# Bread_2040.net
KiCad netlist of a schematic drawn in EAGLE
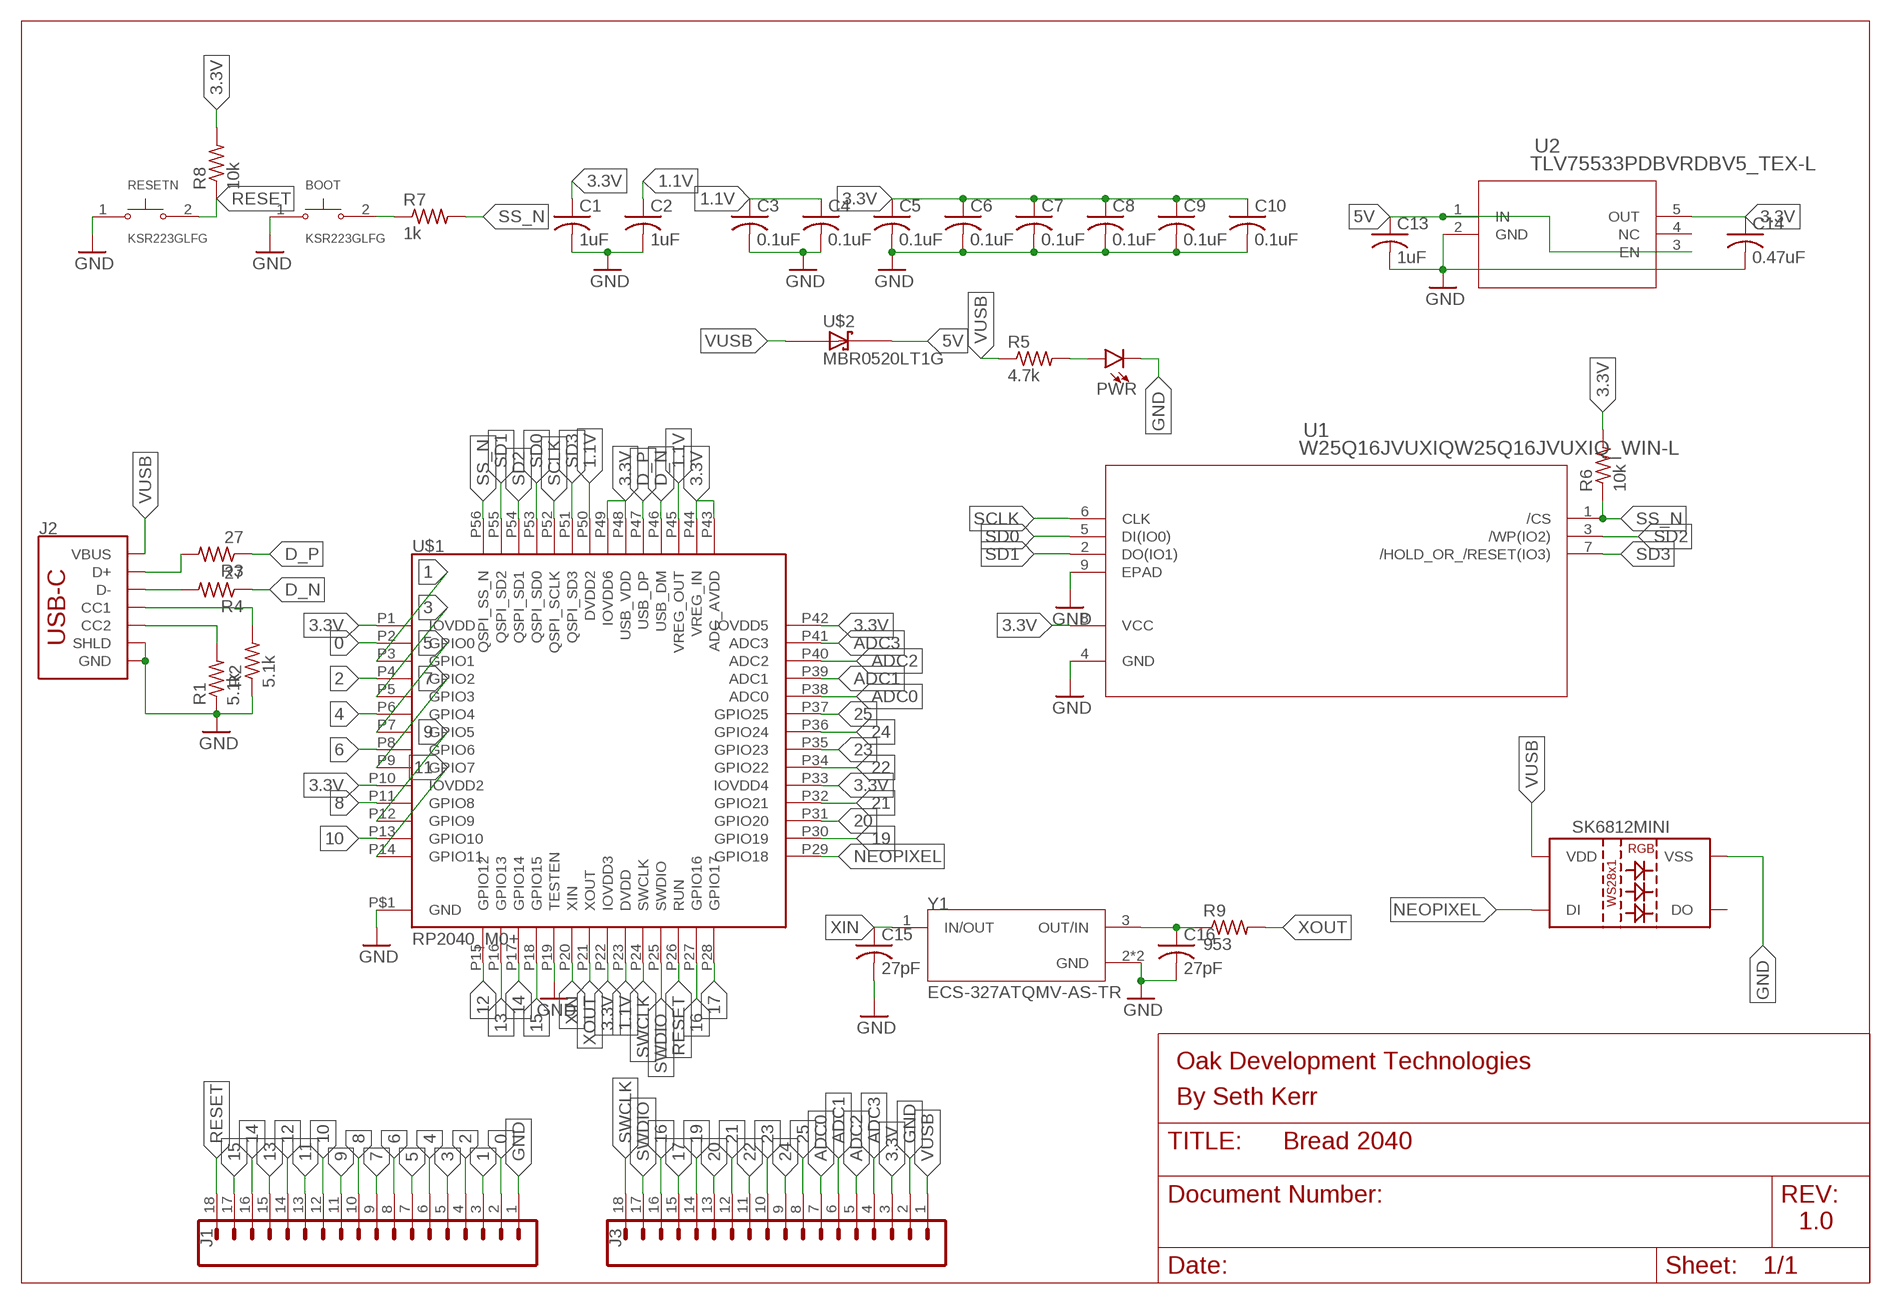
[diagram p0: schematic, sheet 1]

(export (version "E")
  (design (tool "Eeschema 10.0.6"))
  (components
    (comp (ref "BOOT")
      (value "KSR223GLFG")
      (footprint "eagle-import:SW_KSR223GLFG")
      (fields (field (name "MF") "C&K"))
      (libsource (lib "eagle-import") (part "KSR223GLFG"))
    )
    (comp (ref "C1")
      (value "1uF")
      (footprint "eagle-import:C0603")
      (libsource (lib "eagle-import") (part "C-USC0603"))
    )
    (comp (ref "C2")
      (value "1uF")
      (footprint "eagle-import:C0603")
      (libsource (lib "eagle-import") (part "C-USC0603"))
    )
    (comp (ref "C3")
      (value "0.1uF")
      (footprint "eagle-import:C0603")
      (libsource (lib "eagle-import") (part "C-USC0603"))
    )
    (comp (ref "C4")
      (value "0.1uF")
      (footprint "eagle-import:C0603")
      (libsource (lib "eagle-import") (part "C-USC0603"))
    )
    (comp (ref "C5")
      (value "0.1uF")
      (footprint "eagle-import:C0603")
      (libsource (lib "eagle-import") (part "C-USC0603"))
    )
    (comp (ref "C6")
      (value "0.1uF")
      (footprint "eagle-import:C0603")
      (libsource (lib "eagle-import") (part "C-USC0603"))
    )
    (comp (ref "C7")
      (value "0.1uF")
      (footprint "eagle-import:C0603")
      (libsource (lib "eagle-import") (part "C-USC0603"))
    )
    (comp (ref "C8")
      (value "0.1uF")
      (footprint "eagle-import:C0603")
      (libsource (lib "eagle-import") (part "C-USC0603"))
    )
    (comp (ref "C9")
      (value "0.1uF")
      (footprint "eagle-import:C0603")
      (libsource (lib "eagle-import") (part "C-USC0603"))
    )
    (comp (ref "C10")
      (value "0.1uF")
      (footprint "eagle-import:C0603")
      (libsource (lib "eagle-import") (part "C-USC0603"))
    )
    (comp (ref "C13")
      (value "1uF")
      (footprint "eagle-import:C0603")
      (libsource (lib "eagle-import") (part "C-USC0603"))
    )
    (comp (ref "C14")
      (value "0.47uF")
      (footprint "eagle-import:C0603")
      (libsource (lib "eagle-import") (part "C-USC0603"))
    )
    (comp (ref "C15")
      (value "27pF")
      (footprint "eagle-import:C0402")
      (libsource (lib "eagle-import") (part "C-USC0402"))
    )
    (comp (ref "C16")
      (value "27pF")
      (footprint "eagle-import:C0402")
      (libsource (lib "eagle-import") (part "C-USC0402"))
    )
    (comp (ref "J1")
      (value "CONN_18")
      (footprint "eagle-import:1X18_NO_SILK")
      (libsource (lib "eagle-import") (part "CONN_18"))
    )
    (comp (ref "J2")
      (value "USB_C_2-LAYER_PADS")
      (footprint "eagle-import:USB-C-16P-2LAYER-PADS")
      (libsource (lib "eagle-import") (part "USB_C_2-LAYER_PADS"))
    )
    (comp (ref "J3")
      (value "CONN_18")
      (footprint "eagle-import:1X18_NO_SILK")
      (libsource (lib "eagle-import") (part "CONN_18"))
    )
    (comp (ref "PWR")
      (value "LED0603")
      (footprint "eagle-import:LED-0603")
      (libsource (lib "eagle-import") (part "LED0603"))
    )
    (comp (ref "R1")
      (value "5.1k")
      (footprint "eagle-import:R0603")
      (libsource (lib "eagle-import") (part "R-US_R0603"))
    )
    (comp (ref "R2")
      (value "5.1k")
      (footprint "eagle-import:R0603")
      (libsource (lib "eagle-import") (part "R-US_R0603"))
    )
    (comp (ref "R3")
      (value "27")
      (footprint "eagle-import:R0603")
      (libsource (lib "eagle-import") (part "R-US_R0603"))
    )
    (comp (ref "R4")
      (value "27")
      (footprint "eagle-import:R0603")
      (libsource (lib "eagle-import") (part "R-US_R0603"))
    )
    (comp (ref "R5")
      (value "4.7k")
      (footprint "eagle-import:R0603")
      (libsource (lib "eagle-import") (part "R-US_R0603"))
    )
    (comp (ref "R6")
      (value "10k")
      (footprint "eagle-import:R0603")
      (libsource (lib "eagle-import") (part "R-US_R0603"))
    )
    (comp (ref "R7")
      (value "1k")
      (footprint "eagle-import:R0603")
      (libsource (lib "eagle-import") (part "R-US_R0603"))
    )
    (comp (ref "R8")
      (value "10k")
      (footprint "eagle-import:R0603")
      (libsource (lib "eagle-import") (part "R-US_R0603"))
    )
    (comp (ref "R9")
      (value "953")
      (footprint "eagle-import:R0402")
      (libsource (lib "eagle-import") (part "R-US_R0402"))
    )
    (comp (ref "RESETN")
      (value "KSR223GLFG")
      (footprint "eagle-import:SW_KSR223GLFG")
      (fields (field (name "MF") "C&K"))
      (libsource (lib "eagle-import") (part "KSR223GLFG"))
    )
    (comp (ref "SK6812MINI")
      (value "WS2812BWS2812B-3535")
      (footprint "eagle-import:WS2812-3535")
      (libsource (lib "eagle-import") (part "WS2812BWS2812B-3535"))
    )
    (comp (ref "U$1")
      (value "RP2040_M0+")
      (footprint "eagle-import:QFN-56")
      (libsource (lib "eagle-import") (part "RP2040_M0+"))
    )
    (comp (ref "U$2")
      (value "MBR0520LT1G")
      (footprint "eagle-import:SOD3716X117(SOD-123)")
      (fields (field (name "MF") "ON Semiconductor"))
      (libsource (lib "eagle-import") (part "MBR0520LT1G"))
    )
    (comp (ref "U1")
      (value "W25Q16JVUXIQW25Q16JVUXIQ_WIN-L")
      (footprint "eagle-import:W25Q16JVUXIQ_WIN-L")
      (fields
        (field (name "MANUFACTURER_PART_NUMBER") "W25Q16JVUXIQ")
        (field (name "COPYRIGHT") "Copyright (C) 2018 Accelerated Designs. All rights reserved")
      )
      (libsource (lib "eagle-import") (part "W25Q16JVUXIQW25Q16JVUXIQ_WIN-L"))
    )
    (comp (ref "U2")
      (value "TLV75533PDBVRDBV5_TEX-L")
      (footprint "eagle-import:DBV5_TEX-L")
      (fields
        (field (name "MANUFACTURER_PART_NUMBER") "TLV75533PDBVR")
        (field (name "COPYRIGHT") "Copyright (C) 2018 Accelerated Designs. All rights reserved")
      )
      (libsource (lib "eagle-import") (part "TLV75533PDBVRDBV5_TEX-L"))
    )
    (comp (ref "Y1")
      (value "ECS-327ATQMV-AS-TR")
      (footprint "eagle-import:XTAL_ECS-327ATQMV-AS-TR")
      (fields (field (name "DIGI-KEY_PART_NUMBER") "XC2826CT-ND") (field (name "MF") "ECS Inc."))
      (libsource (lib "eagle-import") (part "ECS-327ATQMV-AS-TR"))
    )
  )
  (nets
    (net (code "1") (name "0") (class "Default")
      (node (ref "J1") (pin "2") (pinfunction "2_2") (pintype "passive"))
      (node (ref "U$1") (pin "P2") (pinfunction "GPIO0_P2") (pintype "bidirectional"))
    )
    (net (code "2") (name "1") (class "Default")
      (node (ref "J1") (pin "3") (pinfunction "3_3") (pintype "passive"))
      (node (ref "U$1") (pin "P3") (pinfunction "GPIO1_P3") (pintype "bidirectional"))
    )
    (net (code "3") (name "1.1V") (class "Default")
      (node (ref "C2") (pin "1") (pinfunction "1_1") (pintype "passive"))
      (node (ref "C3") (pin "1") (pinfunction "1_1") (pintype "passive"))
      (node (ref "C4") (pin "1") (pinfunction "1_1") (pintype "passive"))
      (node (ref "U$1") (pin "P23") (pinfunction "DVDD_P23") (pintype "bidirectional"))
      (node (ref "U$1") (pin "P45") (pinfunction "VREG_OUT_P45") (pintype "bidirectional"))
      (node (ref "U$1") (pin "P50") (pinfunction "DVDD2_P50") (pintype "bidirectional"))
    )
    (net (code "4") (name "2") (class "Default")
      (node (ref "J1") (pin "4") (pinfunction "4_4") (pintype "passive"))
      (node (ref "U$1") (pin "P4") (pinfunction "GPIO2_P4") (pintype "bidirectional"))
    )
    (net (code "5") (name "3") (class "Default")
      (node (ref "J1") (pin "5") (pinfunction "5_5") (pintype "passive"))
      (node (ref "U$1") (pin "P5") (pinfunction "GPIO3_P5") (pintype "bidirectional"))
    )
    (net (code "6") (name "3.3V") (class "Default")
      (node (ref "C1") (pin "1") (pinfunction "1_1") (pintype "passive"))
      (node (ref "C10") (pin "1") (pinfunction "1_1") (pintype "passive"))
      (node (ref "C14") (pin "1") (pinfunction "1_1") (pintype "passive"))
      (node (ref "C5") (pin "1") (pinfunction "1_1") (pintype "passive"))
      (node (ref "C6") (pin "1") (pinfunction "1_1") (pintype "passive"))
      (node (ref "C7") (pin "1") (pinfunction "1_1") (pintype "passive"))
      (node (ref "C8") (pin "1") (pinfunction "1_1") (pintype "passive"))
      (node (ref "C9") (pin "1") (pinfunction "1_1") (pintype "passive"))
      (node (ref "J3") (pin "3") (pinfunction "3_3") (pintype "passive"))
      (node (ref "R6") (pin "2") (pinfunction "2_2") (pintype "passive"))
      (node (ref "R8") (pin "2") (pinfunction "2_2") (pintype "passive"))
      (node (ref "U$1") (pin "P1") (pinfunction "IOVDD_P1") (pintype "bidirectional"))
      (node (ref "U$1") (pin "P10") (pinfunction "IOVDD2_P10") (pintype "bidirectional"))
      (node (ref "U$1") (pin "P22") (pinfunction "IOVDD3_P22") (pintype "bidirectional"))
      (node (ref "U$1") (pin "P33") (pinfunction "IOVDD4_P33") (pintype "bidirectional"))
      (node (ref "U$1") (pin "P42") (pinfunction "IOVDD5_P42") (pintype "bidirectional"))
      (node (ref "U$1") (pin "P43") (pinfunction "ADC_AVDD_P43") (pintype "bidirectional"))
      (node (ref "U$1") (pin "P44") (pinfunction "VREG_IN_P44") (pintype "bidirectional"))
      (node (ref "U$1") (pin "P48") (pinfunction "USB_VDD_P48") (pintype "bidirectional"))
      (node (ref "U$1") (pin "P49") (pinfunction "IOVDD6_P49") (pintype "bidirectional"))
      (node (ref "U1") (pin "8") (pinfunction "VCC_8") (pintype "passive"))
      (node (ref "U2") (pin "5") (pinfunction "OUT_5") (pintype "output"))
    )
    (net (code "7") (name "4") (class "Default")
      (node (ref "J1") (pin "6") (pinfunction "6_6") (pintype "passive"))
      (node (ref "U$1") (pin "P6") (pinfunction "GPIO4_P6") (pintype "bidirectional"))
    )
    (net (code "8") (name "5") (class "Default")
      (node (ref "J1") (pin "7") (pinfunction "7_7") (pintype "passive"))
      (node (ref "U$1") (pin "P7") (pinfunction "GPIO5_P7") (pintype "bidirectional"))
    )
    (net (code "9") (name "5V") (class "Default")
      (node (ref "C13") (pin "1") (pinfunction "1_1") (pintype "passive"))
      (node (ref "U$2") (pin "1") (pinfunction "C_1") (pintype "passive"))
      (node (ref "U2") (pin "1") (pinfunction "IN_1") (pintype "input"))
      (node (ref "U2") (pin "3") (pinfunction "EN_3") (pintype "input"))
    )
    (net (code "10") (name "6") (class "Default")
      (node (ref "J1") (pin "8") (pinfunction "8_8") (pintype "passive"))
      (node (ref "U$1") (pin "P8") (pinfunction "GPIO6_P8") (pintype "bidirectional"))
    )
    (net (code "11") (name "7") (class "Default")
      (node (ref "J1") (pin "9") (pinfunction "9_9") (pintype "passive"))
      (node (ref "U$1") (pin "P9") (pinfunction "GPIO7_P9") (pintype "bidirectional"))
    )
    (net (code "12") (name "8") (class "Default")
      (node (ref "J1") (pin "10") (pinfunction "10_10") (pintype "passive"))
      (node (ref "U$1") (pin "P11") (pinfunction "GPIO8_P11") (pintype "bidirectional"))
    )
    (net (code "13") (name "9") (class "Default")
      (node (ref "J1") (pin "11") (pinfunction "11_11") (pintype "passive"))
      (node (ref "U$1") (pin "P12") (pinfunction "GPIO9_P12") (pintype "bidirectional"))
    )
    (net (code "14") (name "10") (class "Default")
      (node (ref "J1") (pin "12") (pinfunction "12_12") (pintype "passive"))
      (node (ref "U$1") (pin "P13") (pinfunction "GPIO10_P13") (pintype "bidirectional"))
    )
    (net (code "15") (name "11") (class "Default")
      (node (ref "J1") (pin "13") (pinfunction "13_13") (pintype "passive"))
      (node (ref "U$1") (pin "P14") (pinfunction "GPIO11_P14") (pintype "bidirectional"))
    )
    (net (code "16") (name "12") (class "Default")
      (node (ref "J1") (pin "14") (pinfunction "14_14") (pintype "passive"))
      (node (ref "U$1") (pin "P15") (pinfunction "GPIO12_P15") (pintype "bidirectional"))
    )
    (net (code "17") (name "13") (class "Default")
      (node (ref "J1") (pin "15") (pinfunction "15_15") (pintype "passive"))
      (node (ref "U$1") (pin "P16") (pinfunction "GPIO13_P16") (pintype "bidirectional"))
    )
    (net (code "18") (name "14") (class "Default")
      (node (ref "J1") (pin "16") (pinfunction "16_16") (pintype "passive"))
      (node (ref "U$1") (pin "P17") (pinfunction "GPIO14_P17") (pintype "bidirectional"))
    )
    (net (code "19") (name "15") (class "Default")
      (node (ref "J1") (pin "17") (pinfunction "17_17") (pintype "passive"))
      (node (ref "U$1") (pin "P18") (pinfunction "GPIO15_P18") (pintype "bidirectional"))
    )
    (net (code "20") (name "16") (class "Default")
      (node (ref "J3") (pin "16") (pinfunction "16_16") (pintype "passive"))
      (node (ref "U$1") (pin "P27") (pinfunction "GPIO16_P27") (pintype "bidirectional"))
    )
    (net (code "21") (name "17") (class "Default")
      (node (ref "J3") (pin "15") (pinfunction "15_15") (pintype "passive"))
      (node (ref "U$1") (pin "P28") (pinfunction "GPIO17_P28") (pintype "bidirectional"))
    )
    (net (code "22") (name "19") (class "Default")
      (node (ref "J3") (pin "14") (pinfunction "14_14") (pintype "passive"))
      (node (ref "U$1") (pin "P30") (pinfunction "GPIO19_P30") (pintype "bidirectional"))
    )
    (net (code "23") (name "20") (class "Default")
      (node (ref "J3") (pin "13") (pinfunction "13_13") (pintype "passive"))
      (node (ref "U$1") (pin "P31") (pinfunction "GPIO20_P31") (pintype "bidirectional"))
    )
    (net (code "24") (name "21") (class "Default")
      (node (ref "J3") (pin "12") (pinfunction "12_12") (pintype "passive"))
      (node (ref "U$1") (pin "P32") (pinfunction "GPIO21_P32") (pintype "bidirectional"))
    )
    (net (code "25") (name "22") (class "Default")
      (node (ref "J3") (pin "11") (pinfunction "11_11") (pintype "passive"))
      (node (ref "U$1") (pin "P34") (pinfunction "GPIO22_P34") (pintype "bidirectional"))
    )
    (net (code "26") (name "23") (class "Default")
      (node (ref "J3") (pin "10") (pinfunction "10_10") (pintype "passive"))
      (node (ref "U$1") (pin "P35") (pinfunction "GPIO23_P35") (pintype "bidirectional"))
    )
    (net (code "27") (name "24") (class "Default")
      (node (ref "J3") (pin "9") (pinfunction "9_9") (pintype "passive"))
      (node (ref "U$1") (pin "P36") (pinfunction "GPIO24_P36") (pintype "bidirectional"))
    )
    (net (code "28") (name "25") (class "Default")
      (node (ref "J3") (pin "8") (pinfunction "8_8") (pintype "passive"))
      (node (ref "U$1") (pin "P37") (pinfunction "GPIO25_P37") (pintype "bidirectional"))
    )
    (net (code "29") (name "ADC0") (class "Default")
      (node (ref "J3") (pin "7") (pinfunction "7_7") (pintype "passive"))
      (node (ref "U$1") (pin "P38") (pinfunction "ADC0_P38") (pintype "bidirectional"))
    )
    (net (code "30") (name "ADC1") (class "Default")
      (node (ref "J3") (pin "6") (pinfunction "6_6") (pintype "passive"))
      (node (ref "U$1") (pin "P39") (pinfunction "ADC1_P39") (pintype "bidirectional"))
    )
    (net (code "31") (name "ADC2") (class "Default")
      (node (ref "J3") (pin "5") (pinfunction "5_5") (pintype "passive"))
      (node (ref "U$1") (pin "P40") (pinfunction "ADC2_P40") (pintype "bidirectional"))
    )
    (net (code "32") (name "ADC3") (class "Default")
      (node (ref "J3") (pin "4") (pinfunction "4_4") (pintype "passive"))
      (node (ref "U$1") (pin "P41") (pinfunction "ADC3_P41") (pintype "bidirectional"))
    )
    (net (code "33") (name "D_N") (class "Default")
      (node (ref "R4") (pin "1") (pinfunction "1_1") (pintype "passive"))
      (node (ref "U$1") (pin "P46") (pinfunction "USB_DM_P46") (pintype "bidirectional"))
    )
    (net (code "34") (name "D_P") (class "Default")
      (node (ref "R3") (pin "1") (pinfunction "1_1") (pintype "passive"))
      (node (ref "U$1") (pin "P47") (pinfunction "USB_DP_P47") (pintype "bidirectional"))
    )
    (net (code "35") (name "GND") (class "Default")
      (node (ref "BOOT") (pin "1") (pinfunction "1_1") (pintype "passive"))
      (node (ref "C1") (pin "2") (pinfunction "2_2") (pintype "passive"))
      (node (ref "C10") (pin "2") (pinfunction "2_2") (pintype "passive"))
      (node (ref "C13") (pin "2") (pinfunction "2_2") (pintype "passive"))
      (node (ref "C14") (pin "2") (pinfunction "2_2") (pintype "passive"))
      (node (ref "C15") (pin "2") (pinfunction "2_2") (pintype "passive"))
      (node (ref "C16") (pin "2") (pinfunction "2_2") (pintype "passive"))
      (node (ref "C2") (pin "2") (pinfunction "2_2") (pintype "passive"))
      (node (ref "C3") (pin "2") (pinfunction "2_2") (pintype "passive"))
      (node (ref "C4") (pin "2") (pinfunction "2_2") (pintype "passive"))
      (node (ref "C5") (pin "2") (pinfunction "2_2") (pintype "passive"))
      (node (ref "C6") (pin "2") (pinfunction "2_2") (pintype "passive"))
      (node (ref "C7") (pin "2") (pinfunction "2_2") (pintype "passive"))
      (node (ref "C8") (pin "2") (pinfunction "2_2") (pintype "passive"))
      (node (ref "C9") (pin "2") (pinfunction "2_2") (pintype "passive"))
      (node (ref "J1") (pin "1") (pinfunction "1_1") (pintype "passive"))
      (node (ref "J2") (pin "GND") (pinfunction "GND_GND") (pintype "bidirectional"))
      (node (ref "J2") (pin "GND2") (pinfunction "GND_GND2") (pintype "bidirectional"))
      (node (ref "J2") (pin "P$1") (pinfunction "SHLD_P$1") (pintype "bidirectional"))
      (node (ref "J2") (pin "P$2") (pinfunction "SHLD_P$2") (pintype "bidirectional"))
      (node (ref "J2") (pin "P$3") (pinfunction "SHLD_P$3") (pintype "bidirectional"))
      (node (ref "J2") (pin "P$4") (pinfunction "SHLD_P$4") (pintype "bidirectional"))
      (node (ref "J2") (pin "SHLD1") (pinfunction "SHLD_SHLD1") (pintype "bidirectional"))
      (node (ref "J2") (pin "SHLD2") (pinfunction "SHLD_SHLD2") (pintype "bidirectional"))
      (node (ref "J2") (pin "SHLD3") (pinfunction "SHLD_SHLD3") (pintype "bidirectional"))
      (node (ref "J2") (pin "SHLD4") (pinfunction "SHLD_SHLD4") (pintype "bidirectional"))
      (node (ref "J3") (pin "2") (pinfunction "2_2") (pintype "passive"))
      (node (ref "PWR") (pin "C") (pinfunction "C_C") (pintype "passive"))
      (node (ref "R1") (pin "1") (pinfunction "1_1") (pintype "passive"))
      (node (ref "R2") (pin "1") (pinfunction "1_1") (pintype "passive"))
      (node (ref "RESETN") (pin "1") (pinfunction "1_1") (pintype "passive"))
      (node (ref "SK6812MINI") (pin "VSS") (pinfunction "VSS_VSS") (pintype "bidirectional"))
      (node (ref "U$1") (pin "P$1") (pinfunction "GND_P$1") (pintype "bidirectional"))
      (node (ref "U$1") (pin "P19") (pinfunction "TESTEN_P19") (pintype "bidirectional"))
      (node (ref "U1") (pin "4") (pinfunction "GND_4") (pintype "passive"))
      (node (ref "U1") (pin "9") (pinfunction "EPAD_9") (pintype "passive"))
      (node (ref "U2") (pin "2") (pinfunction "GND_2") (pintype "power_in"))
      (node (ref "Y1") (pin "2") (pinfunction "GND_2") (pintype "power_in"))
      (node (ref "Y1") (pin "4") (pinfunction "GND_4") (pintype "power_in"))
    )
    (net (code "36") (name "NEOPIXEL") (class "Default")
      (node (ref "SK6812MINI") (pin "DIN") (pinfunction "DI_DIN") (pintype "bidirectional"))
      (node (ref "U$1") (pin "P29") (pinfunction "GPIO18_P29") (pintype "bidirectional"))
    )
    (net (code "37") (name "Net-(BOOT-Pad2)") (class "Default")
      (node (ref "BOOT") (pin "2") (pinfunction "2_2") (pintype "passive"))
      (node (ref "R7") (pin "1") (pinfunction "1_1") (pintype "passive"))
    )
    (net (code "38") (name "Net-(J2-CC1)") (class "Default")
      (node (ref "J2") (pin "A5") (pinfunction "CC1_A5") (pintype "bidirectional"))
      (node (ref "R2") (pin "2") (pinfunction "2_2") (pintype "passive"))
    )
    (net (code "39") (name "Net-(J2-CC2)") (class "Default")
      (node (ref "J2") (pin "B5") (pinfunction "CC2_B5") (pintype "bidirectional"))
      (node (ref "R1") (pin "2") (pinfunction "2_2") (pintype "passive"))
    )
    (net (code "40") (name "Net-(J2-D+-PadA6)") (class "Default")
      (node (ref "J2") (pin "A6") (pinfunction "D+_A6") (pintype "bidirectional"))
      (node (ref "J2") (pin "B6") (pinfunction "D+_B6") (pintype "bidirectional"))
      (node (ref "R3") (pin "2") (pinfunction "2_2") (pintype "passive"))
    )
    (net (code "41") (name "Net-(J2-D--PadA7)") (class "Default")
      (node (ref "J2") (pin "A7") (pinfunction "D-_A7") (pintype "bidirectional"))
      (node (ref "J2") (pin "B7") (pinfunction "D-_B7") (pintype "bidirectional"))
      (node (ref "R4") (pin "2") (pinfunction "2_2") (pintype "passive"))
    )
    (net (code "42") (name "Net-(PWR-PadA)") (class "Default")
      (node (ref "PWR") (pin "A") (pinfunction "A_A") (pintype "passive"))
      (node (ref "R5") (pin "2") (pinfunction "2_2") (pintype "passive"))
    )
    (net (code "43") (name "Net-(Y1-OUT{slash}IN)") (class "Default")
      (node (ref "C16") (pin "1") (pinfunction "1_1") (pintype "passive"))
      (node (ref "R9") (pin "1") (pinfunction "1_1") (pintype "passive"))
      (node (ref "Y1") (pin "3") (pinfunction "OUT/IN_3") (pintype "bidirectional"))
    )
    (net (code "44") (name "RESET") (class "Default")
      (node (ref "J1") (pin "18") (pinfunction "18_18") (pintype "passive"))
      (node (ref "R8") (pin "1") (pinfunction "1_1") (pintype "passive"))
      (node (ref "RESETN") (pin "2") (pinfunction "2_2") (pintype "passive"))
      (node (ref "U$1") (pin "P26") (pinfunction "RUN_P26") (pintype "bidirectional"))
    )
    (net (code "45") (name "SCLK") (class "Default")
      (node (ref "U$1") (pin "P52") (pinfunction "QSPI_SCLK_P52") (pintype "bidirectional"))
      (node (ref "U1") (pin "6") (pinfunction "CLK_6") (pintype "passive"))
    )
    (net (code "46") (name "SD0") (class "Default")
      (node (ref "U$1") (pin "P53") (pinfunction "QSPI_SD0_P53") (pintype "bidirectional"))
      (node (ref "U1") (pin "5") (pinfunction "DI(IO0)_5") (pintype "passive"))
    )
    (net (code "47") (name "SD1") (class "Default")
      (node (ref "U$1") (pin "P55") (pinfunction "QSPI_SD2_P55") (pintype "bidirectional"))
      (node (ref "U1") (pin "2") (pinfunction "DO(IO1)_2") (pintype "passive"))
    )
    (net (code "48") (name "SD2") (class "Default")
      (node (ref "U$1") (pin "P54") (pinfunction "QSPI_SD1_P54") (pintype "bidirectional"))
      (node (ref "U1") (pin "3") (pinfunction "/WP(IO2)_3") (pintype "passive"))
    )
    (net (code "49") (name "SD3") (class "Default")
      (node (ref "U$1") (pin "P51") (pinfunction "QSPI_SD3_P51") (pintype "bidirectional"))
      (node (ref "U1") (pin "7") (pinfunction "/HOLD_OR_/RESET(IO3)_7") (pintype "passive"))
    )
    (net (code "50") (name "SS_N") (class "Default")
      (node (ref "R6") (pin "1") (pinfunction "1_1") (pintype "passive"))
      (node (ref "R7") (pin "2") (pinfunction "2_2") (pintype "passive"))
      (node (ref "U$1") (pin "P56") (pinfunction "QSPI_SS_N_P56") (pintype "bidirectional"))
      (node (ref "U1") (pin "1") (pinfunction "/CS_1") (pintype "passive"))
    )
    (net (code "51") (name "SWCLK") (class "Default")
      (node (ref "J3") (pin "18") (pinfunction "18_18") (pintype "passive"))
      (node (ref "U$1") (pin "P24") (pinfunction "SWCLK_P24") (pintype "bidirectional"))
    )
    (net (code "52") (name "SWDIO") (class "Default")
      (node (ref "J3") (pin "17") (pinfunction "17_17") (pintype "passive"))
      (node (ref "U$1") (pin "P25") (pinfunction "SWDIO_P25") (pintype "bidirectional"))
    )
    (net (code "53") (name "VUSB") (class "Default")
      (node (ref "J2") (pin "VBUS1") (pinfunction "VBUS_VBUS1") (pintype "bidirectional"))
      (node (ref "J2") (pin "VBUS2") (pinfunction "VBUS_VBUS2") (pintype "bidirectional"))
      (node (ref "J3") (pin "1") (pinfunction "1_1") (pintype "passive"))
      (node (ref "R5") (pin "1") (pinfunction "1_1") (pintype "passive"))
      (node (ref "SK6812MINI") (pin "VDD") (pinfunction "VDD_VDD") (pintype "bidirectional"))
      (node (ref "U$2") (pin "2") (pinfunction "A_2") (pintype "passive"))
    )
    (net (code "54") (name "XIN") (class "Default")
      (node (ref "C15") (pin "1") (pinfunction "1_1") (pintype "passive"))
      (node (ref "U$1") (pin "P20") (pinfunction "XIN_P20") (pintype "bidirectional"))
      (node (ref "Y1") (pin "1") (pinfunction "IN/OUT_1") (pintype "bidirectional"))
    )
    (net (code "55") (name "XOUT") (class "Default")
      (node (ref "R9") (pin "2") (pinfunction "2_2") (pintype "passive"))
      (node (ref "U$1") (pin "P21") (pinfunction "XOUT_P21") (pintype "bidirectional"))
    )
    (net (code "56") (name "unconnected-(SK6812MINI-DO-PadDOUT)") (class "Default")
      (node (ref "SK6812MINI") (pin "DOUT") (pinfunction "DO_DOUT") (pintype "bidirectional"))
    )
    (net (code "57") (name "unconnected-(U2-NC-Pad4)") (class "Default")
      (node (ref "U2") (pin "4") (pinfunction "NC_4") (pintype "no_connect"))
    )
  )
)
